# fet_overdrive_v40.net
KiCad netlist of a schematic drawn in EAGLE
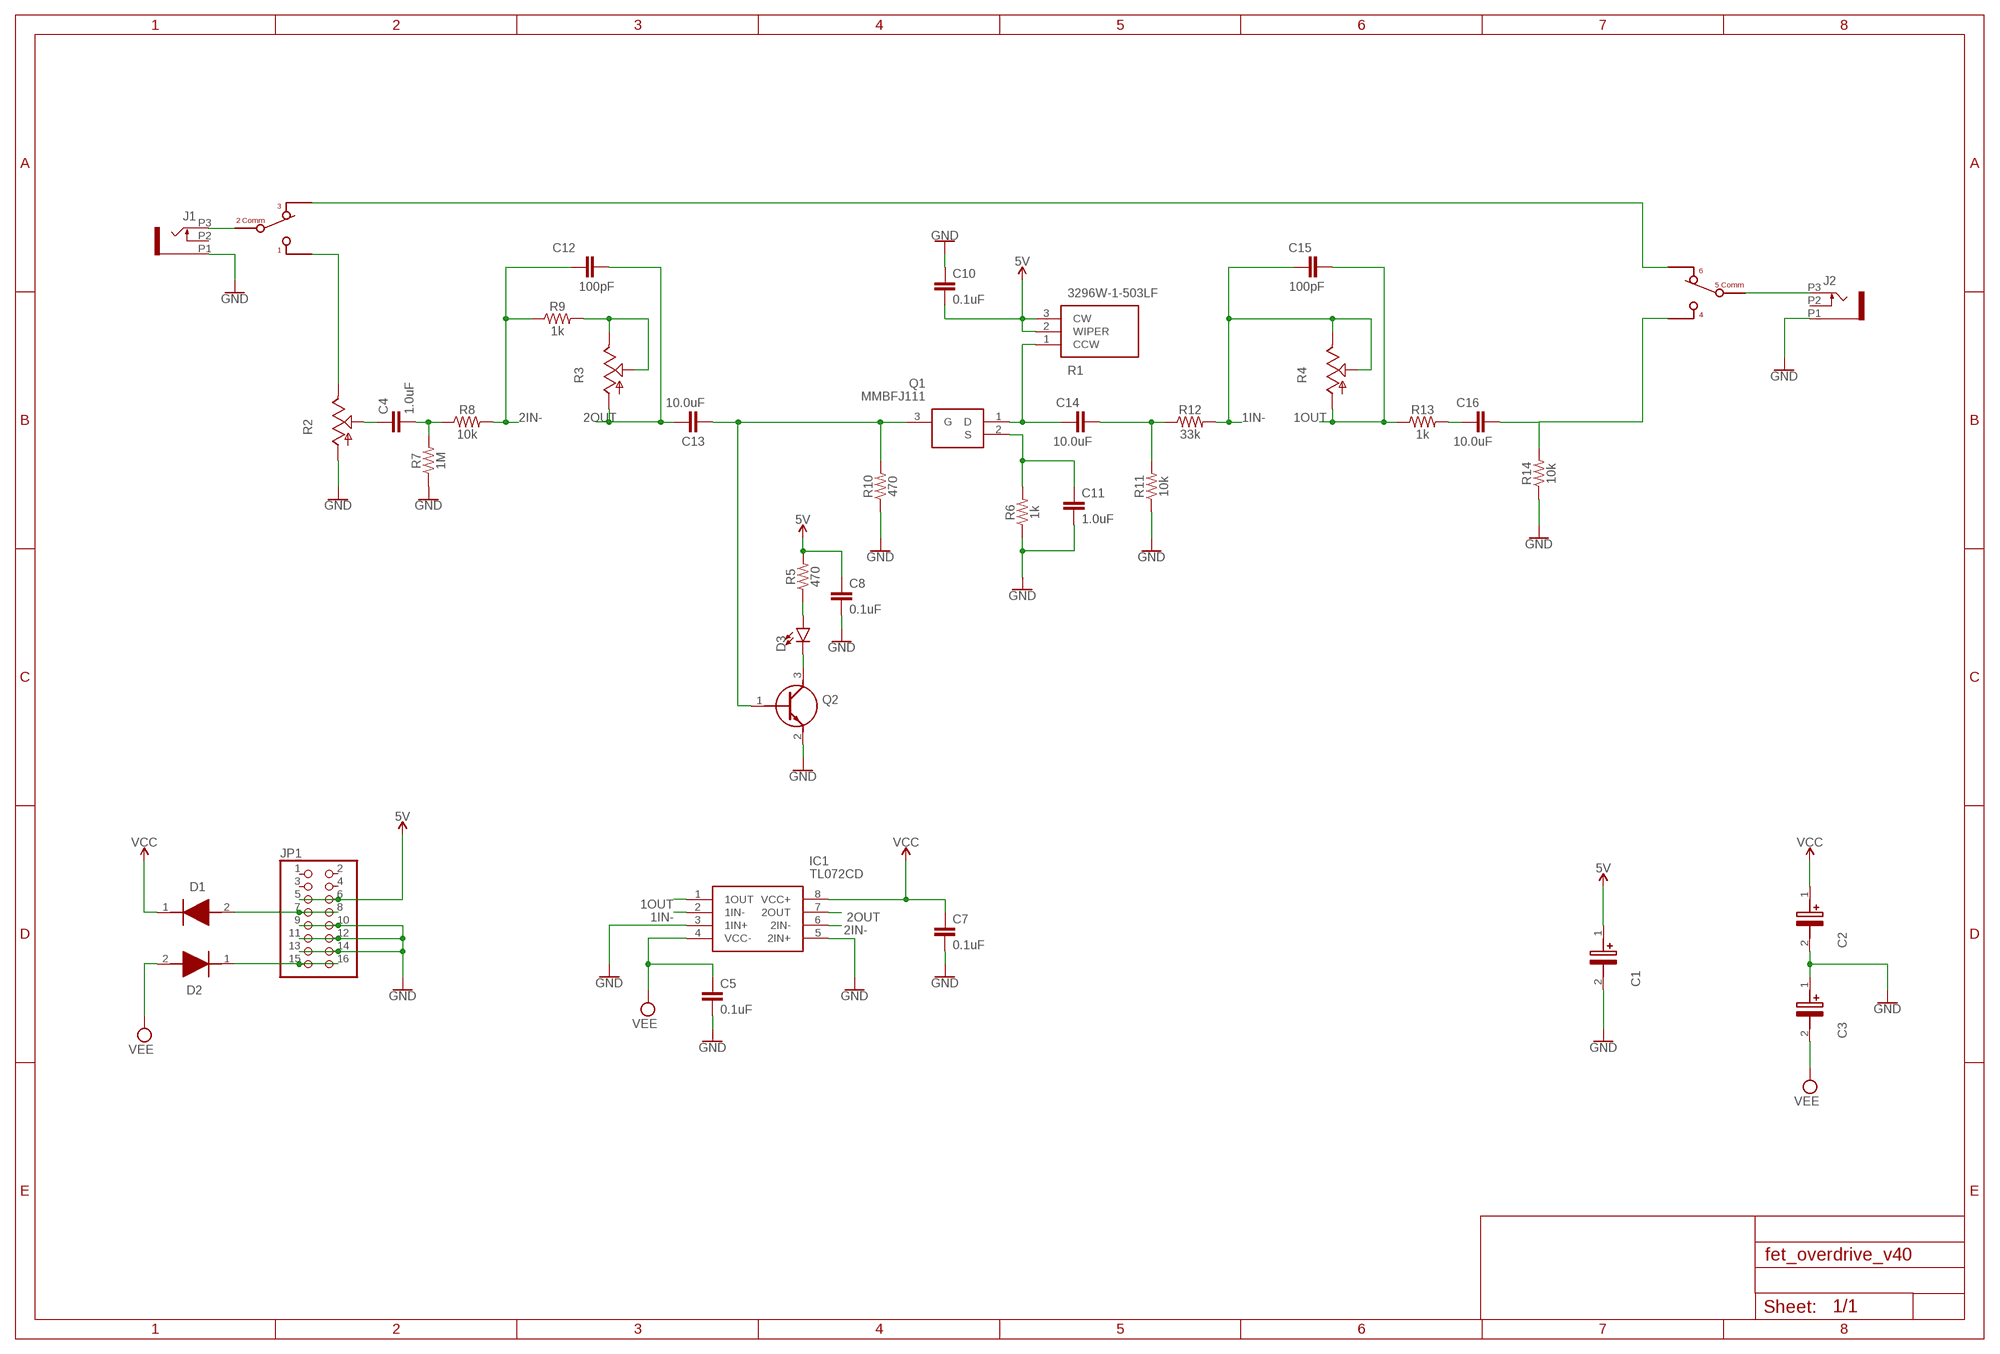
[diagram p0: schematic, sheet 1]

(export (version "E")
  (design (tool "Eeschema 10.0.6"))
  (components
    (comp (ref "C1")
      (value "EEE-FP1E220AR")
      (footprint "eagle-import:EEE0GA101SR")
      (fields (field (name "MOUSER_PART_NUMBER") "667-EEE-FP1E220AR"))
      (libsource (lib "eagle-import") (part "EEE-FP1E220AR"))
    )
    (comp (ref "C2")
      (value "EEE-FK1V470P")
      (footprint "eagle-import:EEE1AA101SP")
      (fields (field (name "MOUSER_PART_NUMBER") "667-EEE-FK1V470P"))
      (libsource (lib "eagle-import") (part "EEE-FK1V470P"))
    )
    (comp (ref "C3")
      (value "EEE-FK1V470P")
      (footprint "eagle-import:EEE1AA101SP")
      (fields (field (name "MOUSER_PART_NUMBER") "667-EEE-FK1V470P"))
      (libsource (lib "eagle-import") (part "EEE-FK1V470P"))
    )
    (comp (ref "C4")
      (value "1.0uF")
      (footprint "eagle-import:0603")
      (libsource (lib "eagle-import") (part "1.0UF-0603-16V-10%"))
    )
    (comp (ref "C5")
      (value "0.1uF")
      (footprint "eagle-import:0603")
      (libsource (lib "eagle-import") (part "0.1UF-0603-25V-5%"))
    )
    (comp (ref "C7")
      (value "0.1uF")
      (footprint "eagle-import:0603")
      (libsource (lib "eagle-import") (part "0.1UF-0603-25V-5%"))
    )
    (comp (ref "C8")
      (value "0.1uF")
      (footprint "eagle-import:0603")
      (libsource (lib "eagle-import") (part "0.1UF-0603-25V-5%"))
    )
    (comp (ref "C10")
      (value "0.1uF")
      (footprint "eagle-import:0603")
      (libsource (lib "eagle-import") (part "0.1UF-0603-25V-5%"))
    )
    (comp (ref "C11")
      (value "1.0uF")
      (footprint "eagle-import:0603")
      (libsource (lib "eagle-import") (part "1.0UF-0603-16V-10%"))
    )
    (comp (ref "C12")
      (value "100pF")
      (footprint "eagle-import:0603")
      (libsource (lib "eagle-import") (part "100PF-0603-50V-5%"))
    )
    (comp (ref "C13")
      (value "10.0uF")
      (footprint "eagle-import:0603")
      (libsource (lib "eagle-import") (part "1.0UF-0603-16V-10%"))
    )
    (comp (ref "C14")
      (value "10.0uF")
      (footprint "eagle-import:0603")
      (libsource (lib "eagle-import") (part "1.0UF-0603-16V-10%"))
    )
    (comp (ref "C15")
      (value "100pF")
      (footprint "eagle-import:0603")
      (libsource (lib "eagle-import") (part "100PF-0603-50V-5%"))
    )
    (comp (ref "C16")
      (value "10.0uF")
      (footprint "eagle-import:0603")
      (libsource (lib "eagle-import") (part "1.0UF-0603-16V-10%"))
    )
    (comp (ref "D1")
      (value "1N5819HW-7-F")
      (footprint "eagle-import:SOD3716X145N")
      (fields (field (name "MOUSER_PART_NUMBER") "621-1N5819HW-F"))
      (libsource (lib "eagle-import") (part "1N5819HW-7-F"))
    )
    (comp (ref "D2")
      (value "1N5819HW-7-F")
      (footprint "eagle-import:SOD3716X145N")
      (fields (field (name "MOUSER_PART_NUMBER") "621-1N5819HW-F"))
      (libsource (lib "eagle-import") (part "1N5819HW-7-F"))
    )
    (comp (ref "D3")
      (value "LED3MM")
      (footprint "eagle-import:LED_3MM")
      (libsource (lib "eagle-import") (part "LED3MM"))
    )
    (comp (ref "IC1")
      (value "TL072CD")
      (footprint "eagle-import:SOIC127P600X175-8N")
      (fields (field (name "MOUSER_PART_NUMBER") "595-TL072CD"))
      (libsource (lib "eagle-import") (part "TL072CD"))
    )
    (comp (ref "J1")
      (value "PJ301_THONKICONN6")
      (footprint "eagle-import:WQP_PJ_301M6")
      (libsource (lib "eagle-import") (part "PJ301_THONKICONN6"))
    )
    (comp (ref "J2")
      (value "PJ301_THONKICONN6")
      (footprint "eagle-import:WQP_PJ_301M6")
      (libsource (lib "eagle-import") (part "PJ301_THONKICONN6"))
    )
    (comp (ref "JP1")
      (value "PINHD-2X8")
      (footprint "eagle-import:2X08")
      (libsource (lib "eagle-import") (part "PINHD-2X8"))
    )
    (comp (ref "Q1")
      (value "MMBFJ111")
      (footprint "eagle-import:SOT96P237X111-3N")
      (fields (field (name "MOUSER_PART_NUMBER") "512-MMBFJ111"))
      (libsource (lib "eagle-import") (part "MMBFJ111"))
    )
    (comp (ref "Q2")
      (value "SMMBT3904LT1G")
      (footprint "eagle-import:SOT96P237X111-3N")
      (fields (field (name "MOUSER_PART_NUMBER") "863-SMMBT3904LT1G"))
      (libsource (lib "eagle-import") (part "SMMBT3904LT1G"))
    )
    (comp (ref "R1")
      (value "3296W-1-503LF")
      (footprint "eagle-import:3296W-1")
      (fields (field (name "MOUSER_PART_NUMBER") "652-3296W-1-503LF"))
      (libsource (lib "eagle-import") (part "3296W-1-503LF"))
    )
    (comp (ref "R2")
      (value "POT_USVERTICAL_PS")
      (footprint "eagle-import:ALPS_POT_VERTICAL_PS")
      (libsource (lib "eagle-import") (part "POT_USVERTICAL_PS"))
    )
    (comp (ref "R3")
      (value "POT_USVERTICAL_PS")
      (footprint "eagle-import:ALPS_POT_VERTICAL_PS")
      (libsource (lib "eagle-import") (part "POT_USVERTICAL_PS"))
    )
    (comp (ref "R4")
      (value "POT_USVERTICAL_PS")
      (footprint "eagle-import:ALPS_POT_VERTICAL_PS")
      (libsource (lib "eagle-import") (part "POT_USVERTICAL_PS"))
    )
    (comp (ref "R5")
      (value "470")
      (footprint "eagle-import:0603")
      (libsource (lib "eagle-import") (part "470OHM-0603-1/10W-1%"))
    )
    (comp (ref "R6")
      (value "1k")
      (footprint "eagle-import:0603")
      (libsource (lib "eagle-import") (part "1KOHM-0603-1/10W-1%"))
    )
    (comp (ref "R7")
      (value "1M")
      (footprint "eagle-import:0603")
      (libsource (lib "eagle-import") (part "1MOHM-0603-1/4W-5%"))
    )
    (comp (ref "R8")
      (value "10k")
      (footprint "eagle-import:0603")
      (libsource (lib "eagle-import") (part "10KOHM-0603-1/10W-1%"))
    )
    (comp (ref "R9")
      (value "1k")
      (footprint "eagle-import:0603")
      (libsource (lib "eagle-import") (part "1KOHM-0603-1/10W-1%"))
    )
    (comp (ref "R10")
      (value "470")
      (footprint "eagle-import:0603")
      (libsource (lib "eagle-import") (part "470OHM-0603-1/10W-1%"))
    )
    (comp (ref "R11")
      (value "10k")
      (footprint "eagle-import:0603")
      (libsource (lib "eagle-import") (part "10KOHM-0603-1/10W-1%"))
    )
    (comp (ref "R12")
      (value "33k")
      (footprint "eagle-import:0603")
      (libsource (lib "eagle-import") (part "33KOHM-0603-1/10W-1%"))
    )
    (comp (ref "R13")
      (value "1k")
      (footprint "eagle-import:0603")
      (libsource (lib "eagle-import") (part "1KOHM-0603-1/10W-1%"))
    )
    (comp (ref "R14")
      (value "10k")
      (footprint "eagle-import:0603")
      (libsource (lib "eagle-import") (part "10KOHM-0603-1/10W-1%"))
    )
    (comp (ref "U$2")
      (value "DAILYWELL-DPDT")
      (footprint "eagle-import:DAILYWELL-DPDT")
      (libsource (lib "eagle-import") (part "DAILYWELL-DPDT"))
    )
  )
  (nets
    (net (code "1") (name "/1IN-") (class "Default")
      (node (ref "C15") (pin "1") (pinfunction "1_1") (pintype "passive"))
      (node (ref "IC1") (pin "2") (pinfunction "1IN-_2") (pintype "bidirectional"))
      (node (ref "R12") (pin "2") (pinfunction "2_2") (pintype "passive"))
      (node (ref "R4") (pin "P$1") (pinfunction "E_P$1") (pintype "passive"))
      (node (ref "R4") (pin "P$2") (pinfunction "S_P$2") (pintype "passive"))
    )
    (net (code "2") (name "/1OUT") (class "Default")
      (node (ref "C15") (pin "2") (pinfunction "2_2") (pintype "passive"))
      (node (ref "IC1") (pin "1") (pinfunction "1OUT_1") (pintype "bidirectional"))
      (node (ref "R13") (pin "1") (pinfunction "1_1") (pintype "passive"))
      (node (ref "R4") (pin "P$3") (pinfunction "A_P$3") (pintype "passive"))
    )
    (net (code "3") (name "/2IN-") (class "Default")
      (node (ref "C12") (pin "1") (pinfunction "1_1") (pintype "passive"))
      (node (ref "IC1") (pin "6") (pinfunction "2IN-_6") (pintype "bidirectional"))
      (node (ref "R8") (pin "2") (pinfunction "2_2") (pintype "passive"))
      (node (ref "R9") (pin "1") (pinfunction "1_1") (pintype "passive"))
    )
    (net (code "4") (name "/2OUT") (class "Default")
      (node (ref "C12") (pin "2") (pinfunction "2_2") (pintype "passive"))
      (node (ref "C13") (pin "1") (pinfunction "1_1") (pintype "passive"))
      (node (ref "IC1") (pin "7") (pinfunction "2OUT_7") (pintype "bidirectional"))
      (node (ref "R3") (pin "P$3") (pinfunction "A_P$3") (pintype "passive"))
    )
    (net (code "5") (name "5V") (class "Default")
      (node (ref "C1") (pin "1") (pinfunction "+_1") (pintype "bidirectional"))
      (node (ref "C10") (pin "2") (pinfunction "2_2") (pintype "passive"))
      (node (ref "C8") (pin "1") (pinfunction "1_1") (pintype "passive"))
      (node (ref "JP1") (pin "5") (pinfunction "5_5") (pintype "passive"))
      (node (ref "JP1") (pin "6") (pinfunction "6_6") (pintype "passive"))
      (node (ref "R1") (pin "2") (pinfunction "WIPER_2") (pintype "bidirectional"))
      (node (ref "R1") (pin "3") (pinfunction "CW_3") (pintype "bidirectional"))
      (node (ref "R5") (pin "2") (pinfunction "2_2") (pintype "passive"))
    )
    (net (code "6") (name "GND") (class "Default")
      (node (ref "C1") (pin "2") (pinfunction "-_2") (pintype "bidirectional"))
      (node (ref "C10") (pin "1") (pinfunction "1_1") (pintype "passive"))
      (node (ref "C11") (pin "2") (pinfunction "2_2") (pintype "passive"))
      (node (ref "C2") (pin "2") (pinfunction "-_2") (pintype "bidirectional"))
      (node (ref "C3") (pin "1") (pinfunction "+_1") (pintype "bidirectional"))
      (node (ref "C5") (pin "2") (pinfunction "2_2") (pintype "passive"))
      (node (ref "C7") (pin "2") (pinfunction "2_2") (pintype "passive"))
      (node (ref "C8") (pin "2") (pinfunction "2_2") (pintype "passive"))
      (node (ref "IC1") (pin "3") (pinfunction "1IN+_3") (pintype "bidirectional"))
      (node (ref "IC1") (pin "5") (pinfunction "2IN+_5") (pintype "bidirectional"))
      (node (ref "J1") (pin "P1") (pinfunction "1_P1") (pintype "passive"))
      (node (ref "J2") (pin "P1") (pinfunction "1_P1") (pintype "passive"))
      (node (ref "JP1") (pin "10") (pinfunction "10_10") (pintype "passive"))
      (node (ref "JP1") (pin "11") (pinfunction "11_11") (pintype "passive"))
      (node (ref "JP1") (pin "12") (pinfunction "12_12") (pintype "passive"))
      (node (ref "JP1") (pin "13") (pinfunction "13_13") (pintype "passive"))
      (node (ref "JP1") (pin "14") (pinfunction "14_14") (pintype "passive"))
      (node (ref "JP1") (pin "9") (pinfunction "9_9") (pintype "passive"))
      (node (ref "Q2") (pin "2") (pinfunction "E_2") (pintype "bidirectional"))
      (node (ref "R10") (pin "1") (pinfunction "1_1") (pintype "passive"))
      (node (ref "R11") (pin "1") (pinfunction "1_1") (pintype "passive"))
      (node (ref "R14") (pin "1") (pinfunction "1_1") (pintype "passive"))
      (node (ref "R2") (pin "P$3") (pinfunction "A_P$3") (pintype "passive"))
      (node (ref "R6") (pin "1") (pinfunction "1_1") (pintype "passive"))
      (node (ref "R7") (pin "1") (pinfunction "1_1") (pintype "passive"))
    )
    (net (code "7") (name "Net-(C4-Pad2)") (class "Default")
      (node (ref "C4") (pin "2") (pinfunction "2_2") (pintype "passive"))
      (node (ref "R7") (pin "2") (pinfunction "2_2") (pintype "passive"))
      (node (ref "R8") (pin "1") (pinfunction "1_1") (pintype "passive"))
    )
    (net (code "8") (name "Net-(C14-Pad2)") (class "Default")
      (node (ref "C14") (pin "2") (pinfunction "2_2") (pintype "passive"))
      (node (ref "R11") (pin "2") (pinfunction "2_2") (pintype "passive"))
      (node (ref "R12") (pin "1") (pinfunction "1_1") (pintype "passive"))
    )
    (net (code "9") (name "Net-(C16-Pad1)") (class "Default")
      (node (ref "C16") (pin "1") (pinfunction "1_1") (pintype "passive"))
      (node (ref "R13") (pin "2") (pinfunction "2_2") (pintype "passive"))
    )
    (net (code "10") (name "Net-(D1-A)") (class "Default")
      (node (ref "D1") (pin "2") (pinfunction "A_2") (pintype "bidirectional"))
      (node (ref "JP1") (pin "7") (pinfunction "7_7") (pintype "passive"))
      (node (ref "JP1") (pin "8") (pinfunction "8_8") (pintype "passive"))
    )
    (net (code "11") (name "Net-(D2-K)") (class "Default")
      (node (ref "D2") (pin "1") (pinfunction "K_1") (pintype "bidirectional"))
      (node (ref "JP1") (pin "15") (pinfunction "15_15") (pintype "passive"))
      (node (ref "JP1") (pin "16") (pinfunction "16_16") (pintype "passive"))
    )
    (net (code "12") (name "Net-(D3-C)") (class "Default")
      (node (ref "D3") (pin "K") (pinfunction "C_K") (pintype "passive"))
      (node (ref "Q2") (pin "3") (pinfunction "C_3") (pintype "bidirectional"))
    )
    (net (code "13") (name "Net-(D3-PadA)") (class "Default")
      (node (ref "D3") (pin "A") (pinfunction "A_A") (pintype "passive"))
      (node (ref "R5") (pin "1") (pinfunction "1_1") (pintype "passive"))
    )
    (net (code "14") (name "Net-(J1-3)") (class "Default")
      (node (ref "J1") (pin "P3") (pinfunction "3_P3") (pintype "passive"))
      (node (ref "U$2") (pin "P$2") (pinfunction "P$2_P$2") (pintype "bidirectional"))
    )
    (net (code "15") (name "Net-(J2-3)") (class "Default")
      (node (ref "J2") (pin "P3") (pinfunction "3_P3") (pintype "passive"))
      (node (ref "U$2") (pin "P$5") (pinfunction "P$2_P$5") (pintype "bidirectional"))
    )
    (net (code "16") (name "Net-(Q1-D)") (class "Default")
      (node (ref "C14") (pin "1") (pinfunction "1_1") (pintype "passive"))
      (node (ref "Q1") (pin "1") (pinfunction "D_1") (pintype "bidirectional"))
      (node (ref "R1") (pin "1") (pinfunction "CCW_1") (pintype "bidirectional"))
    )
    (net (code "17") (name "Net-(Q1-G)") (class "Default")
      (node (ref "C13") (pin "2") (pinfunction "2_2") (pintype "passive"))
      (node (ref "Q1") (pin "3") (pinfunction "G_3") (pintype "bidirectional"))
      (node (ref "Q2") (pin "1") (pinfunction "B_1") (pintype "bidirectional"))
      (node (ref "R10") (pin "2") (pinfunction "2_2") (pintype "passive"))
    )
    (net (code "18") (name "Net-(Q1-S)") (class "Default")
      (node (ref "C11") (pin "1") (pinfunction "1_1") (pintype "passive"))
      (node (ref "Q1") (pin "2") (pinfunction "S_2") (pintype "bidirectional"))
      (node (ref "R6") (pin "2") (pinfunction "2_2") (pintype "passive"))
    )
    (net (code "19") (name "Net-(R2-E)") (class "Default")
      (node (ref "R2") (pin "P$1") (pinfunction "E_P$1") (pintype "passive"))
      (node (ref "U$2") (pin "P$1") (pinfunction "P$1_P$1") (pintype "bidirectional"))
    )
    (net (code "20") (name "Net-(R2-S)") (class "Default")
      (node (ref "C4") (pin "1") (pinfunction "1_1") (pintype "passive"))
      (node (ref "R2") (pin "P$2") (pinfunction "S_P$2") (pintype "passive"))
    )
    (net (code "21") (name "Net-(R3-E)") (class "Default")
      (node (ref "R3") (pin "P$1") (pinfunction "E_P$1") (pintype "passive"))
      (node (ref "R3") (pin "P$2") (pinfunction "S_P$2") (pintype "passive"))
      (node (ref "R9") (pin "2") (pinfunction "2_2") (pintype "passive"))
    )
    (net (code "22") (name "Net-(U$2B-P$1)") (class "Default")
      (node (ref "C16") (pin "2") (pinfunction "2_2") (pintype "passive"))
      (node (ref "R14") (pin "2") (pinfunction "2_2") (pintype "passive"))
      (node (ref "U$2") (pin "P$4") (pinfunction "P$1_P$4") (pintype "bidirectional"))
    )
    (net (code "23") (name "Net-(U$2B-P$3)") (class "Default")
      (node (ref "U$2") (pin "P$3") (pinfunction "P$3_P$3") (pintype "bidirectional"))
      (node (ref "U$2") (pin "P$6") (pinfunction "P$3_P$6") (pintype "bidirectional"))
    )
    (net (code "24") (name "VCC") (class "Default")
      (node (ref "C2") (pin "1") (pinfunction "+_1") (pintype "bidirectional"))
      (node (ref "C7") (pin "1") (pinfunction "1_1") (pintype "passive"))
      (node (ref "D1") (pin "1") (pinfunction "K_1") (pintype "bidirectional"))
      (node (ref "IC1") (pin "8") (pinfunction "VCC+_8") (pintype "bidirectional"))
    )
    (net (code "25") (name "VEE") (class "Default")
      (node (ref "C3") (pin "2") (pinfunction "-_2") (pintype "bidirectional"))
      (node (ref "C5") (pin "1") (pinfunction "1_1") (pintype "passive"))
      (node (ref "D2") (pin "2") (pinfunction "A_2") (pintype "bidirectional"))
      (node (ref "IC1") (pin "4") (pinfunction "VCC-_4") (pintype "bidirectional"))
    )
    (net (code "26") (name "unconnected-(J1-2-PadP2)") (class "Default")
      (node (ref "J1") (pin "P2") (pinfunction "2_P2") (pintype "passive"))
    )
    (net (code "27") (name "unconnected-(J2-2-PadP2)") (class "Default")
      (node (ref "J2") (pin "P2") (pinfunction "2_P2") (pintype "passive"))
    )
    (net (code "28") (name "unconnected-(JP1-Pad1)") (class "Default")
      (node (ref "JP1") (pin "1") (pinfunction "1_1") (pintype "passive"))
    )
    (net (code "29") (name "unconnected-(JP1-Pad2)") (class "Default")
      (node (ref "JP1") (pin "2") (pinfunction "2_2") (pintype "passive"))
    )
    (net (code "30") (name "unconnected-(JP1-Pad3)") (class "Default")
      (node (ref "JP1") (pin "3") (pinfunction "3_3") (pintype "passive"))
    )
    (net (code "31") (name "unconnected-(JP1-Pad4)") (class "Default")
      (node (ref "JP1") (pin "4") (pinfunction "4_4") (pintype "passive"))
    )
  )
)
